# beacon7012.net
KiCad netlist of a schematic drawn in EAGLE
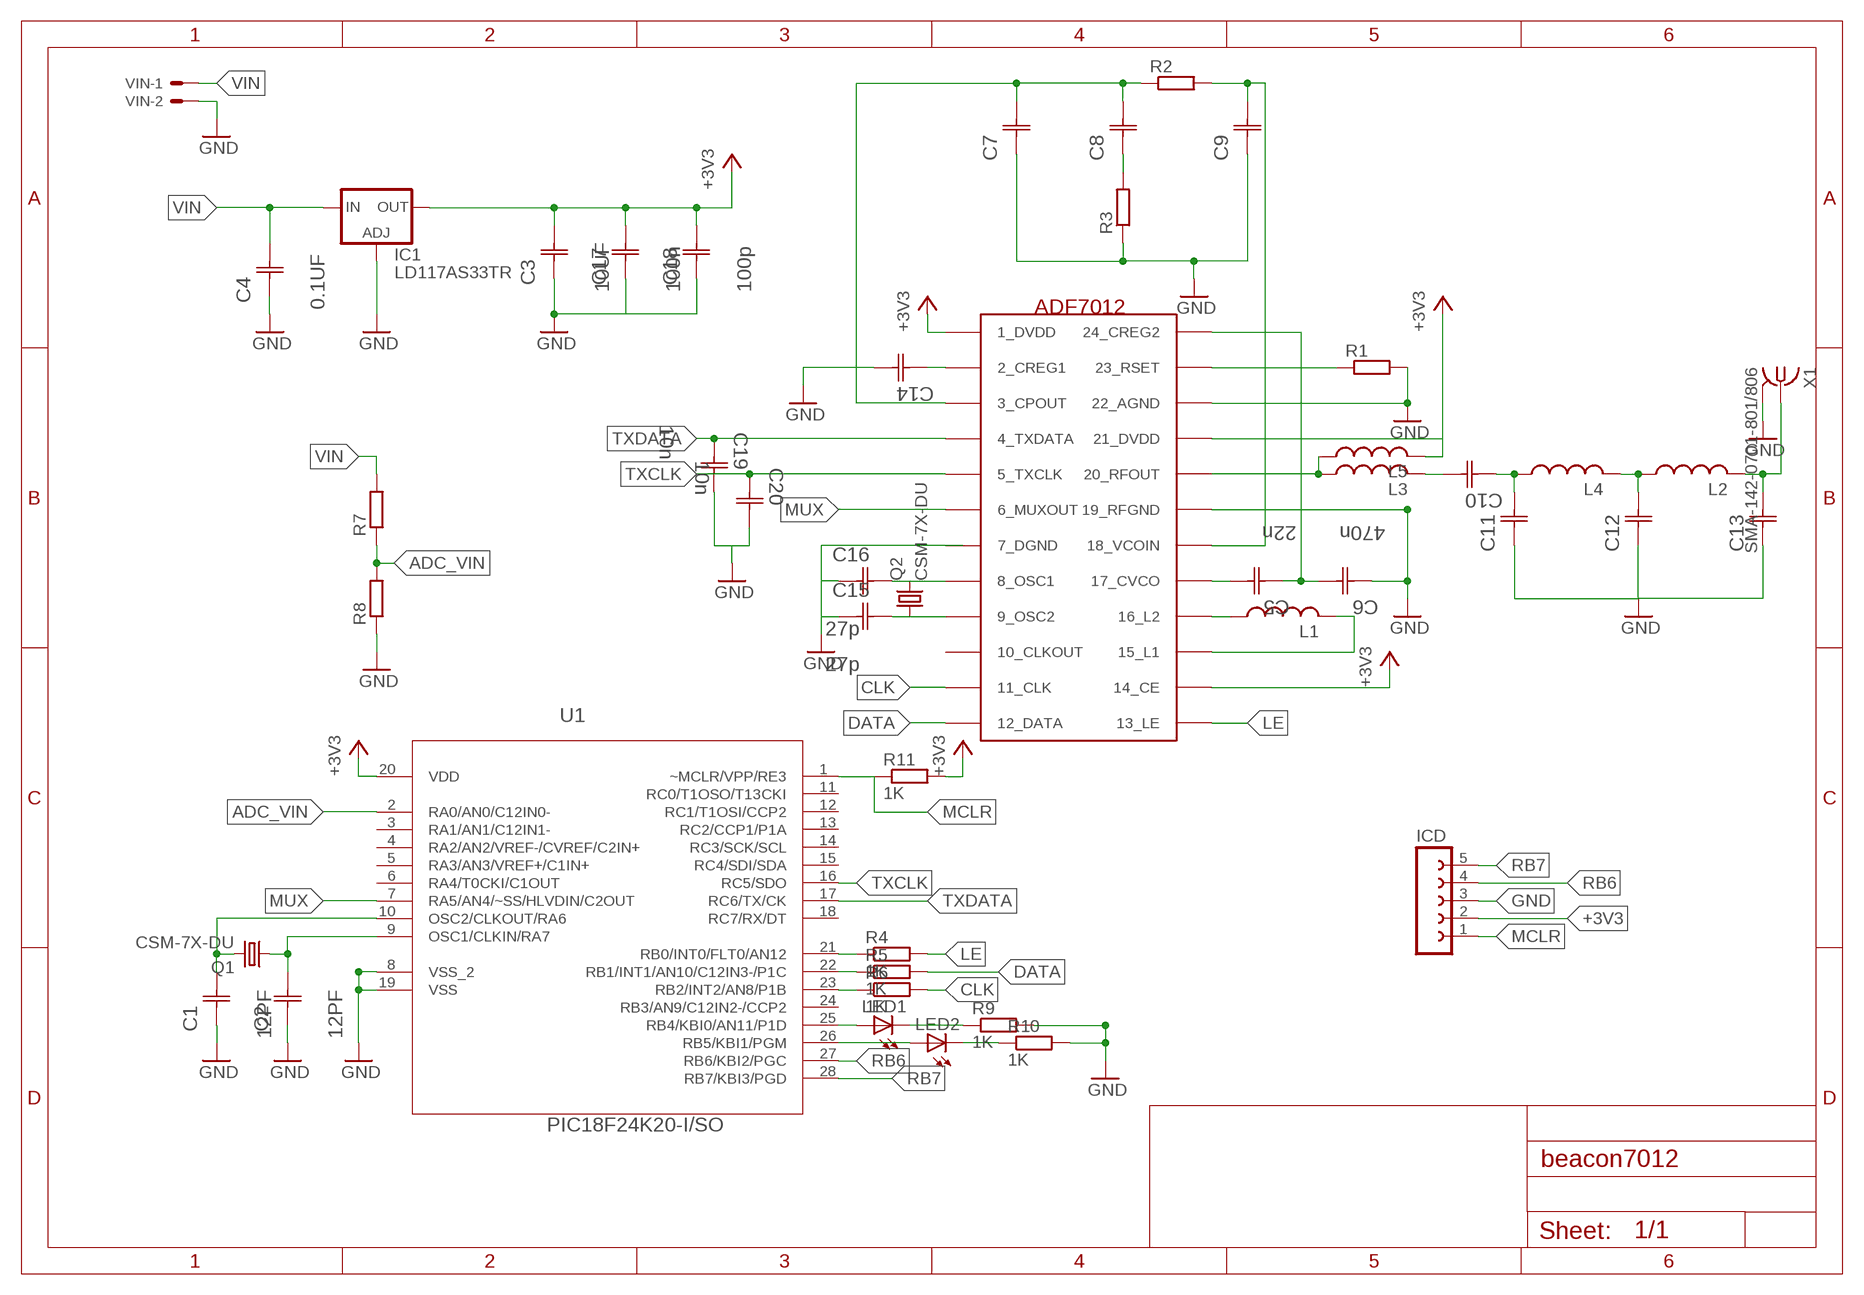
[diagram p0: schematic, sheet 1]

(export (version "E")
  (design (tool "Eeschema 10.0.6"))
  (components
    (comp (ref "C1")
      (value "12PF")
      (footprint "eagle-import:CAPC2012X94N")
      (fields (field (name "MPN") "0805YA120JAT2A") (field (name "TOLERANCE") "± 5%"))
      (libsource (lib "eagle-import") (part "0805YA120JAT2A"))
    )
    (comp (ref "C2")
      (value "12PF")
      (footprint "eagle-import:CAPC2012X94N")
      (fields (field (name "MPN") "0805YA120JAT2A") (field (name "TOLERANCE") "± 5%"))
      (libsource (lib "eagle-import") (part "0805YA120JAT2A"))
    )
    (comp (ref "C3")
      (value "10UF")
      (footprint "eagle-import:CAPC2013X140N")
      (fields (field (name "MPN") "0805YD106MAT2A") (field (name "TOLERANCE") "±20%"))
      (libsource (lib "eagle-import") (part "0805YD106MAT2A"))
    )
    (comp (ref "C4")
      (value "0.1UF")
      (footprint "eagle-import:CAPC2012X94N")
      (fields (field (name "MPN") "0805ZC104MAT2A") (field (name "TOLERANCE") "±20%"))
      (libsource (lib "eagle-import") (part "0805ZC104MAT2A"))
    )
    (comp (ref "C5")
      (value "22n")
      (footprint "eagle-import:CAPC2012X94N")
      (fields (field (name "MPN") "0805ZC104MAT2A") (field (name "TOLERANCE") "±20%"))
      (libsource (lib "eagle-import") (part "0805ZC104MAT2A"))
    )
    (comp (ref "C6")
      (value "470n")
      (footprint "eagle-import:CAPC2012X94N")
      (fields (field (name "MPN") "0805ZC104MAT2A") (field (name "TOLERANCE") "±20%"))
      (libsource (lib "eagle-import") (part "0805ZC104MAT2A"))
    )
    (comp (ref "C7")
      (value "0805YD106MAT2A")
      (footprint "eagle-import:CAPC2013X140N")
      (fields (field (name "TOLERANCE") "±20%"))
      (libsource (lib "eagle-import") (part "0805YD106MAT2A"))
    )
    (comp (ref "C8")
      (value "0805YD106MAT2A")
      (footprint "eagle-import:CAPC2013X140N")
      (fields (field (name "TOLERANCE") "±20%"))
      (libsource (lib "eagle-import") (part "0805YD106MAT2A"))
    )
    (comp (ref "C9")
      (value "0805YD106MAT2A")
      (footprint "eagle-import:CAPC2013X140N")
      (fields (field (name "TOLERANCE") "±20%"))
      (libsource (lib "eagle-import") (part "0805YD106MAT2A"))
    )
    (comp (ref "C10")
      (value "0805ZC104MAT2A")
      (footprint "eagle-import:CAPC2012X94N")
      (fields (field (name "TOLERANCE") "±20%"))
      (libsource (lib "eagle-import") (part "0805ZC104MAT2A"))
    )
    (comp (ref "C11")
      (value "0805YD106MAT2A")
      (footprint "eagle-import:CAPC2013X140N")
      (fields (field (name "TOLERANCE") "±20%"))
      (libsource (lib "eagle-import") (part "0805YD106MAT2A"))
    )
    (comp (ref "C12")
      (value "0805YD106MAT2A")
      (footprint "eagle-import:CAPC2013X140N")
      (fields (field (name "TOLERANCE") "±20%"))
      (libsource (lib "eagle-import") (part "0805YD106MAT2A"))
    )
    (comp (ref "C13")
      (value "0805YD106MAT2A")
      (footprint "eagle-import:CAPC2013X140N")
      (fields (field (name "TOLERANCE") "±20%"))
      (libsource (lib "eagle-import") (part "0805YD106MAT2A"))
    )
    (comp (ref "C14")
      (value "0805ZC104MAT2A")
      (footprint "eagle-import:CAPC2012X94N")
      (fields (field (name "TOLERANCE") "±20%"))
      (libsource (lib "eagle-import") (part "0805ZC104MAT2A"))
    )
    (comp (ref "C15")
      (value "27p")
      (footprint "eagle-import:CAPC2012X94N")
      (fields (field (name "MPN") "0805ZC104MAT2A") (field (name "TOLERANCE") "±20%"))
      (libsource (lib "eagle-import") (part "0805ZC104MAT2A"))
    )
    (comp (ref "C16")
      (value "27p")
      (footprint "eagle-import:CAPC2012X94N")
      (fields (field (name "MPN") "0805ZC104MAT2A") (field (name "TOLERANCE") "±20%"))
      (libsource (lib "eagle-import") (part "0805ZC104MAT2A"))
    )
    (comp (ref "C17")
      (value "100n")
      (footprint "eagle-import:CAPC2013X140N")
      (fields (field (name "MPN") "0805YD106MAT2A") (field (name "TOLERANCE") "±20%"))
      (libsource (lib "eagle-import") (part "0805YD106MAT2A"))
    )
    (comp (ref "C18")
      (value "100p")
      (footprint "eagle-import:CAPC2013X140N")
      (fields (field (name "MPN") "0805YD106MAT2A") (field (name "TOLERANCE") "±20%"))
      (libsource (lib "eagle-import") (part "0805YD106MAT2A"))
    )
    (comp (ref "C19")
      (value "10n")
      (footprint "eagle-import:CAPC2012X94N")
      (fields (field (name "MPN") "0805ZC104MAT2A") (field (name "TOLERANCE") "±20%"))
      (libsource (lib "eagle-import") (part "0805ZC104MAT2A"))
    )
    (comp (ref "C20")
      (value "10n")
      (footprint "eagle-import:CAPC2012X94N")
      (fields (field (name "MPN") "0805ZC104MAT2A") (field (name "TOLERANCE") "±20%"))
      (libsource (lib "eagle-import") (part "0805ZC104MAT2A"))
    )
    (comp (ref "IC1")
      (value "LD117AS33TR")
      (footprint "eagle-import:SOT223")
      (libsource (lib "eagle-import") (part "LD117A?S33TR"))
    )
    (comp (ref "ICD")
      (value "FE05-1")
      (footprint "eagle-import:FE05-1")
      (libsource (lib "eagle-import") (part "FE05-1"))
    )
    (comp (ref "L1")
      (value "L-USL2825P")
      (footprint "eagle-import:L2825P")
      (libsource (lib "eagle-import") (part "L-USL2825P"))
    )
    (comp (ref "L2")
      (value "L-USL2825P")
      (footprint "eagle-import:L2825P")
      (libsource (lib "eagle-import") (part "L-USL2825P"))
    )
    (comp (ref "L3")
      (value "L-USL2825P")
      (footprint "eagle-import:L2825P")
      (libsource (lib "eagle-import") (part "L-USL2825P"))
    )
    (comp (ref "L4")
      (value "L-USL2825P")
      (footprint "eagle-import:L2825P")
      (libsource (lib "eagle-import") (part "L-USL2825P"))
    )
    (comp (ref "L5")
      (value "L-USL2825P")
      (footprint "eagle-import:L2825P")
      (libsource (lib "eagle-import") (part "L-USL2825P"))
    )
    (comp (ref "LED1")
      (value "LEDSML0805")
      (footprint "eagle-import:SML0805")
      (libsource (lib "eagle-import") (part "LEDSML0805"))
    )
    (comp (ref "LED2")
      (value "LEDSML0805")
      (footprint "eagle-import:SML0805")
      (libsource (lib "eagle-import") (part "LEDSML0805"))
    )
    (comp (ref "Q1")
      (value "CSM-7X-DU")
      (footprint "eagle-import:CSM-7X-DU")
      (libsource (lib "eagle-import") (part "CSM-7X-DU"))
    )
    (comp (ref "Q2")
      (value "CSM-7X-DU")
      (footprint "eagle-import:CSM-7X-DU")
      (libsource (lib "eagle-import") (part "CSM-7X-DU"))
    )
    (comp (ref "R1")
      (value "R-EU_R0805")
      (footprint "eagle-import:R0805")
      (libsource (lib "eagle-import") (part "R-EU_R0805"))
    )
    (comp (ref "R2")
      (value "R-EU_R0805")
      (footprint "eagle-import:R0805")
      (libsource (lib "eagle-import") (part "R-EU_R0805"))
    )
    (comp (ref "R3")
      (value "R-EU_R0805")
      (footprint "eagle-import:R0805")
      (libsource (lib "eagle-import") (part "R-EU_R0805"))
    )
    (comp (ref "R4")
      (value "1K")
      (footprint "eagle-import:R0805")
      (libsource (lib "eagle-import") (part "R-EU_R0805"))
    )
    (comp (ref "R5")
      (value "1K")
      (footprint "eagle-import:R0805")
      (libsource (lib "eagle-import") (part "R-EU_R0805"))
    )
    (comp (ref "R6")
      (value "1K")
      (footprint "eagle-import:R0805")
      (libsource (lib "eagle-import") (part "R-EU_R0805"))
    )
    (comp (ref "R7")
      (value "R-EU_R0805")
      (footprint "eagle-import:R0805")
      (libsource (lib "eagle-import") (part "R-EU_R0805"))
    )
    (comp (ref "R8")
      (value "R-EU_R0805")
      (footprint "eagle-import:R0805")
      (libsource (lib "eagle-import") (part "R-EU_R0805"))
    )
    (comp (ref "R9")
      (value "1K")
      (footprint "eagle-import:R0805")
      (libsource (lib "eagle-import") (part "R-EU_R0805"))
    )
    (comp (ref "R10")
      (value "1K")
      (footprint "eagle-import:R0805")
      (libsource (lib "eagle-import") (part "R-EU_R0805"))
    )
    (comp (ref "R11")
      (value "1K")
      (footprint "eagle-import:R0805")
      (libsource (lib "eagle-import") (part "R-EU_R0805"))
    )
    (comp (ref "U$1")
      (value "ADF7012")
      (footprint "eagle-import:ADF7012")
      (libsource (lib "eagle-import") (part "ADF7012"))
    )
    (comp (ref "U1")
      (value "PIC18F24K20-I/SO")
      (footprint "eagle-import:SOIC127P1030X265-28N")
      (libsource (lib "eagle-import") (part "PIC18F24K20-I/SO"))
    )
    (comp (ref "VIN")
      (value "KK-156-2")
      (footprint "eagle-import:KK-156-2")
      (libsource (lib "eagle-import") (part "KK-156-2"))
    )
    (comp (ref "X1")
      (value "SMA-142-0701-801/806")
      (footprint "eagle-import:J502-ND-142-0701-801_806")
      (fields (field (name "MF") "JOHNSON COMPONENTS") (field (name "MPN") "142-0701-801"))
      (libsource (lib "eagle-import") (part "SMA-142-0701-801/806"))
    )
  )
  (nets
    (net (code "1") (name "+3V3") (class "Default")
      (node (ref "C17") (pin "2") (pinfunction "C2_2") (pintype "passive"))
      (node (ref "C18") (pin "2") (pinfunction "C2_2") (pintype "passive"))
      (node (ref "C3") (pin "2") (pinfunction "C2_2") (pintype "passive"))
      (node (ref "IC1") (pin "4") (pinfunction "OUT_4") (pintype "passive"))
      (node (ref "ICD") (pin "2") (pinfunction "2_2") (pintype "passive"))
      (node (ref "L5") (pin "2") (pinfunction "2_2") (pintype "passive"))
      (node (ref "R11") (pin "2") (pinfunction "2_2") (pintype "passive"))
      (node (ref "U$1") (pin "14_CE") (pinfunction "14_CE_14_CE") (pintype "bidirectional"))
      (node (ref "U$1") (pin "1_DVDD") (pinfunction "1_DVDD_1_DVDD") (pintype "bidirectional"))
      (node (ref "U$1") (pin "21_DVDD") (pinfunction "21_DVDD_21_DVDD") (pintype "bidirectional"))
      (node (ref "U1") (pin "20") (pinfunction "VDD_20") (pintype "power_in"))
    )
    (net (code "2") (name "ADC_VIN") (class "Default")
      (node (ref "R7") (pin "1") (pinfunction "1_1") (pintype "passive"))
      (node (ref "R8") (pin "2") (pinfunction "2_2") (pintype "passive"))
      (node (ref "U1") (pin "2") (pinfunction "RA0/AN0/C12IN0-_2") (pintype "bidirectional"))
    )
    (net (code "3") (name "CLK") (class "Default")
      (node (ref "R6") (pin "2") (pinfunction "2_2") (pintype "passive"))
      (node (ref "U$1") (pin "11_CLK") (pinfunction "11_CLK_11_CLK") (pintype "bidirectional"))
    )
    (net (code "4") (name "DATA") (class "Default")
      (node (ref "R5") (pin "2") (pinfunction "2_2") (pintype "passive"))
      (node (ref "U$1") (pin "12_DATA") (pinfunction "12_DATA_12_DATA") (pintype "bidirectional"))
    )
    (net (code "5") (name "GND") (class "Default")
      (node (ref "C1") (pin "1") (pinfunction "C1_1") (pintype "passive"))
      (node (ref "C11") (pin "1") (pinfunction "C1_1") (pintype "passive"))
      (node (ref "C12") (pin "1") (pinfunction "C1_1") (pintype "passive"))
      (node (ref "C13") (pin "1") (pinfunction "C1_1") (pintype "passive"))
      (node (ref "C14") (pin "2") (pinfunction "C2_2") (pintype "passive"))
      (node (ref "C15") (pin "1") (pinfunction "C1_1") (pintype "passive"))
      (node (ref "C16") (pin "1") (pinfunction "C1_1") (pintype "passive"))
      (node (ref "C17") (pin "1") (pinfunction "C1_1") (pintype "passive"))
      (node (ref "C18") (pin "1") (pinfunction "C1_1") (pintype "passive"))
      (node (ref "C19") (pin "2") (pinfunction "C2_2") (pintype "passive"))
      (node (ref "C2") (pin "1") (pinfunction "C1_1") (pintype "passive"))
      (node (ref "C20") (pin "2") (pinfunction "C2_2") (pintype "passive"))
      (node (ref "C3") (pin "1") (pinfunction "C1_1") (pintype "passive"))
      (node (ref "C4") (pin "1") (pinfunction "C1_1") (pintype "passive"))
      (node (ref "C6") (pin "1") (pinfunction "C1_1") (pintype "passive"))
      (node (ref "C7") (pin "1") (pinfunction "C1_1") (pintype "passive"))
      (node (ref "C9") (pin "1") (pinfunction "C1_1") (pintype "passive"))
      (node (ref "IC1") (pin "1") (pinfunction "ADJ_1") (pintype "input"))
      (node (ref "ICD") (pin "3") (pinfunction "3_3") (pintype "passive"))
      (node (ref "R1") (pin "2") (pinfunction "2_2") (pintype "passive"))
      (node (ref "R10") (pin "2") (pinfunction "2_2") (pintype "passive"))
      (node (ref "R3") (pin "1") (pinfunction "1_1") (pintype "passive"))
      (node (ref "R8") (pin "1") (pinfunction "1_1") (pintype "passive"))
      (node (ref "R9") (pin "2") (pinfunction "2_2") (pintype "passive"))
      (node (ref "U$1") (pin "19_RFGND") (pinfunction "19_RFGND_19_RFGND") (pintype "bidirectional"))
      (node (ref "U$1") (pin "22_AGND") (pinfunction "22_AGND_22_AGND") (pintype "bidirectional"))
      (node (ref "U1") (pin "19") (pinfunction "VSS_19") (pintype "power_in"))
      (node (ref "U1") (pin "8") (pinfunction "VSS_2_8") (pintype "power_in"))
      (node (ref "VIN") (pin "2") (pinfunction "S_2") (pintype "passive"))
      (node (ref "X1") (pin "G@1") (pinfunction "2_G@1") (pintype "passive"))
      (node (ref "X1") (pin "G@2") (pinfunction "2_G@2") (pintype "passive"))
      (node (ref "X1") (pin "G@3") (pinfunction "2_G@3") (pintype "passive"))
      (node (ref "X1") (pin "G@4") (pinfunction "2_G@4") (pintype "passive"))
    )
    (net (code "6") (name "LE") (class "Default")
      (node (ref "R4") (pin "2") (pinfunction "2_2") (pintype "passive"))
      (node (ref "U$1") (pin "13_LE") (pinfunction "13_LE_13_LE") (pintype "bidirectional"))
    )
    (net (code "7") (name "MCLR") (class "Default")
      (node (ref "ICD") (pin "1") (pinfunction "1_1") (pintype "passive"))
      (node (ref "R11") (pin "1") (pinfunction "1_1") (pintype "passive"))
      (node (ref "U1") (pin "1") (pinfunction "~{MCLR/VPP/RE3}_1") (pintype "bidirectional"))
    )
    (net (code "8") (name "MUX") (class "Default")
      (node (ref "U$1") (pin "6_MUXOUT") (pinfunction "6_MUXOUT_6_MUXOUT") (pintype "bidirectional"))
      (node (ref "U1") (pin "7") (pinfunction "RA5/AN4/~{SS/HLVDIN/C2OUT}_7") (pintype "bidirectional"))
    )
    (net (code "9") (name "Net-(C1-C2)") (class "Default")
      (node (ref "C1") (pin "2") (pinfunction "C2_2") (pintype "passive"))
      (node (ref "Q1") (pin "2") (pinfunction "2_2") (pintype "passive"))
      (node (ref "U1") (pin "10") (pinfunction "OSC2/CLKOUT/RA6_10") (pintype "bidirectional"))
    )
    (net (code "10") (name "Net-(C2-C2)") (class "Default")
      (node (ref "C2") (pin "2") (pinfunction "C2_2") (pintype "passive"))
      (node (ref "Q1") (pin "1") (pinfunction "1_1") (pintype "passive"))
      (node (ref "U1") (pin "9") (pinfunction "OSC1/CLKIN/RA7_9") (pintype "bidirectional"))
    )
    (net (code "11") (name "Net-(C5-C1)") (class "Default")
      (node (ref "C5") (pin "1") (pinfunction "C1_1") (pintype "passive"))
      (node (ref "C6") (pin "2") (pinfunction "C2_2") (pintype "passive"))
      (node (ref "U$1") (pin "24_CREG2") (pinfunction "24_CREG2_24_CREG2") (pintype "bidirectional"))
    )
    (net (code "12") (name "Net-(C5-C2)") (class "Default")
      (node (ref "C5") (pin "2") (pinfunction "C2_2") (pintype "passive"))
      (node (ref "U$1") (pin "17_CVCO") (pinfunction "17_CVCO_17_CVCO") (pintype "bidirectional"))
    )
    (net (code "13") (name "Net-(C7-C2)") (class "Default")
      (node (ref "C7") (pin "2") (pinfunction "C2_2") (pintype "passive"))
      (node (ref "C8") (pin "2") (pinfunction "C2_2") (pintype "passive"))
      (node (ref "R2") (pin "1") (pinfunction "1_1") (pintype "passive"))
      (node (ref "U$1") (pin "3_CPOUT") (pinfunction "3_CPOUT_3_CPOUT") (pintype "bidirectional"))
    )
    (net (code "14") (name "Net-(C8-C1)") (class "Default")
      (node (ref "C8") (pin "1") (pinfunction "C1_1") (pintype "passive"))
      (node (ref "R3") (pin "2") (pinfunction "2_2") (pintype "passive"))
    )
    (net (code "15") (name "Net-(C9-C2)") (class "Default")
      (node (ref "C9") (pin "2") (pinfunction "C2_2") (pintype "passive"))
      (node (ref "R2") (pin "2") (pinfunction "2_2") (pintype "passive"))
      (node (ref "U$1") (pin "18_VCOIN") (pinfunction "18_VCOIN_18_VCOIN") (pintype "bidirectional"))
    )
    (net (code "16") (name "Net-(C10-C1)") (class "Default")
      (node (ref "C10") (pin "1") (pinfunction "C1_1") (pintype "passive"))
      (node (ref "C11") (pin "2") (pinfunction "C2_2") (pintype "passive"))
      (node (ref "L4") (pin "1") (pinfunction "1_1") (pintype "passive"))
    )
    (net (code "17") (name "Net-(C10-C2)") (class "Default")
      (node (ref "C10") (pin "2") (pinfunction "C2_2") (pintype "passive"))
      (node (ref "L3") (pin "2") (pinfunction "2_2") (pintype "passive"))
    )
    (net (code "18") (name "Net-(C12-C2)") (class "Default")
      (node (ref "C12") (pin "2") (pinfunction "C2_2") (pintype "passive"))
      (node (ref "L2") (pin "1") (pinfunction "1_1") (pintype "passive"))
      (node (ref "L4") (pin "2") (pinfunction "2_2") (pintype "passive"))
    )
    (net (code "19") (name "Net-(C13-C2)") (class "Default")
      (node (ref "C13") (pin "2") (pinfunction "C2_2") (pintype "passive"))
      (node (ref "L2") (pin "2") (pinfunction "2_2") (pintype "passive"))
      (node (ref "X1") (pin "1") (pinfunction "1_1") (pintype "passive"))
    )
    (net (code "20") (name "Net-(C14-C1)") (class "Default")
      (node (ref "C14") (pin "1") (pinfunction "C1_1") (pintype "passive"))
      (node (ref "U$1") (pin "2_CREG1") (pinfunction "2_CREG1_2_CREG1") (pintype "bidirectional"))
    )
    (net (code "21") (name "Net-(C15-C2)") (class "Default")
      (node (ref "C15") (pin "2") (pinfunction "C2_2") (pintype "passive"))
      (node (ref "Q2") (pin "1") (pinfunction "1_1") (pintype "passive"))
      (node (ref "U$1") (pin "9_OSC2") (pinfunction "9_OSC2_9_OSC2") (pintype "bidirectional"))
    )
    (net (code "22") (name "Net-(C16-C2)") (class "Default")
      (node (ref "C16") (pin "2") (pinfunction "C2_2") (pintype "passive"))
      (node (ref "Q2") (pin "2") (pinfunction "2_2") (pintype "passive"))
      (node (ref "U$1") (pin "8_OSC1") (pinfunction "8_OSC1_8_OSC1") (pintype "bidirectional"))
    )
    (net (code "23") (name "Net-(L1-Pad1)") (class "Default")
      (node (ref "L1") (pin "1") (pinfunction "1_1") (pintype "passive"))
      (node (ref "U$1") (pin "16_L2") (pinfunction "16_L2_16_L2") (pintype "bidirectional"))
    )
    (net (code "24") (name "Net-(L1-Pad2)") (class "Default")
      (node (ref "L1") (pin "2") (pinfunction "2_2") (pintype "passive"))
      (node (ref "U$1") (pin "15_L1") (pinfunction "15_L1_15_L1") (pintype "bidirectional"))
    )
    (net (code "25") (name "Net-(L3-Pad1)") (class "Default")
      (node (ref "L3") (pin "1") (pinfunction "1_1") (pintype "passive"))
      (node (ref "L5") (pin "1") (pinfunction "1_1") (pintype "passive"))
      (node (ref "U$1") (pin "20_RFOUT") (pinfunction "20_RFOUT_20_RFOUT") (pintype "bidirectional"))
    )
    (net (code "26") (name "Net-(LED1-PadC)") (class "Default")
      (node (ref "LED1") (pin "C") (pinfunction "C_C") (pintype "passive"))
      (node (ref "R9") (pin "1") (pinfunction "1_1") (pintype "passive"))
    )
    (net (code "27") (name "Net-(LED2-PadC)") (class "Default")
      (node (ref "LED2") (pin "C") (pinfunction "C_C") (pintype "passive"))
      (node (ref "R10") (pin "1") (pinfunction "1_1") (pintype "passive"))
    )
    (net (code "28") (name "Net-(R1-Pad1)") (class "Default")
      (node (ref "R1") (pin "1") (pinfunction "1_1") (pintype "passive"))
      (node (ref "U$1") (pin "23_RSET") (pinfunction "23_RSET_23_RSET") (pintype "bidirectional"))
    )
    (net (code "29") (name "Net-(U1-RB0{slash}INT0{slash}FLT0{slash}AN12)") (class "Default")
      (node (ref "R4") (pin "1") (pinfunction "1_1") (pintype "passive"))
      (node (ref "U1") (pin "21") (pinfunction "RB0/INT0/FLT0/AN12_21") (pintype "bidirectional"))
    )
    (net (code "30") (name "Net-(U1-RB1{slash}INT1{slash}AN10{slash}C12IN3-{slash}P1C)") (class "Default")
      (node (ref "R5") (pin "1") (pinfunction "1_1") (pintype "passive"))
      (node (ref "U1") (pin "22") (pinfunction "RB1/INT1/AN10/C12IN3-/P1C_22") (pintype "bidirectional"))
    )
    (net (code "31") (name "Net-(U1-RB2{slash}INT2{slash}AN8{slash}P1B)") (class "Default")
      (node (ref "R6") (pin "1") (pinfunction "1_1") (pintype "passive"))
      (node (ref "U1") (pin "23") (pinfunction "RB2/INT2/AN8/P1B_23") (pintype "bidirectional"))
    )
    (net (code "32") (name "Net-(U1-RB4{slash}KBI0{slash}AN11{slash}P1D)") (class "Default")
      (node (ref "LED1") (pin "A") (pinfunction "A_A") (pintype "passive"))
      (node (ref "U1") (pin "25") (pinfunction "RB4/KBI0/AN11/P1D_25") (pintype "bidirectional"))
    )
    (net (code "33") (name "Net-(U1-RB5{slash}KBI1{slash}PGM)") (class "Default")
      (node (ref "LED2") (pin "A") (pinfunction "A_A") (pintype "passive"))
      (node (ref "U1") (pin "26") (pinfunction "RB5/KBI1/PGM_26") (pintype "bidirectional"))
    )
    (net (code "34") (name "RB6") (class "Default")
      (node (ref "ICD") (pin "4") (pinfunction "4_4") (pintype "passive"))
      (node (ref "U1") (pin "27") (pinfunction "RB6/KBI2/PGC_27") (pintype "bidirectional"))
    )
    (net (code "35") (name "RB7") (class "Default")
      (node (ref "ICD") (pin "5") (pinfunction "5_5") (pintype "passive"))
      (node (ref "U1") (pin "28") (pinfunction "RB7/KBI3/PGD_28") (pintype "bidirectional"))
    )
    (net (code "36") (name "TXCLK") (class "Default")
      (node (ref "C20") (pin "1") (pinfunction "C1_1") (pintype "passive"))
      (node (ref "U$1") (pin "5_TXCLK") (pinfunction "5_TXCLK_5_TXCLK") (pintype "bidirectional"))
      (node (ref "U1") (pin "16") (pinfunction "RC5/SDO_16") (pintype "bidirectional"))
    )
    (net (code "37") (name "TXDATA") (class "Default")
      (node (ref "C19") (pin "1") (pinfunction "C1_1") (pintype "passive"))
      (node (ref "U$1") (pin "4_TXDATA") (pinfunction "4_TXDATA_4_TXDATA") (pintype "bidirectional"))
      (node (ref "U1") (pin "17") (pinfunction "RC6/TX/CK_17") (pintype "bidirectional"))
    )
    (net (code "38") (name "VIN") (class "Default")
      (node (ref "C4") (pin "2") (pinfunction "C2_2") (pintype "passive"))
      (node (ref "IC1") (pin "3") (pinfunction "IN_3") (pintype "input"))
      (node (ref "R7") (pin "2") (pinfunction "2_2") (pintype "passive"))
      (node (ref "VIN") (pin "1") (pinfunction "S_1") (pintype "passive"))
    )
    (net (code "39") (name "unconnected-(U$1-Pad7_DGND)") (class "Default")
      (node (ref "U$1") (pin "7_DGND") (pinfunction "7_DGND_7_DGND") (pintype "bidirectional"))
    )
    (net (code "40") (name "unconnected-(U$1-Pad10_CLKOUT)") (class "Default")
      (node (ref "U$1") (pin "10_CLKOUT") (pinfunction "10_CLKOUT_10_CLKOUT") (pintype "bidirectional"))
    )
    (net (code "41") (name "unconnected-(U1-RA1{slash}AN1{slash}C12IN1--Pad3)") (class "Default")
      (node (ref "U1") (pin "3") (pinfunction "RA1/AN1/C12IN1-_3") (pintype "bidirectional"))
    )
    (net (code "42") (name "unconnected-(U1-RA2{slash}AN2{slash}VREF-{slash}CVREF{slash}C2IN+-Pad4)") (class "Default")
      (node (ref "U1") (pin "4") (pinfunction "RA2/AN2/VREF-/CVREF/C2IN+_4") (pintype "bidirectional"))
    )
    (net (code "43") (name "unconnected-(U1-RA3{slash}AN3{slash}VREF+{slash}C1IN+-Pad5)") (class "Default")
      (node (ref "U1") (pin "5") (pinfunction "RA3/AN3/VREF+/C1IN+_5") (pintype "bidirectional"))
    )
    (net (code "44") (name "unconnected-(U1-RA4{slash}T0CKI{slash}C1OUT-Pad6)") (class "Default")
      (node (ref "U1") (pin "6") (pinfunction "RA4/T0CKI/C1OUT_6") (pintype "bidirectional"))
    )
    (net (code "45") (name "unconnected-(U1-RB3{slash}AN9{slash}C12IN2-{slash}CCP2-Pad24)") (class "Default")
      (node (ref "U1") (pin "24") (pinfunction "RB3/AN9/C12IN2-/CCP2_24") (pintype "bidirectional"))
    )
    (net (code "46") (name "unconnected-(U1-RC0{slash}T1OSO{slash}T13CKI-Pad11)") (class "Default")
      (node (ref "U1") (pin "11") (pinfunction "RC0/T1OSO/T13CKI_11") (pintype "bidirectional"))
    )
    (net (code "47") (name "unconnected-(U1-RC1{slash}T1OSI{slash}CCP2-Pad12)") (class "Default")
      (node (ref "U1") (pin "12") (pinfunction "RC1/T1OSI/CCP2_12") (pintype "bidirectional"))
    )
    (net (code "48") (name "unconnected-(U1-RC2{slash}CCP1{slash}P1A-Pad13)") (class "Default")
      (node (ref "U1") (pin "13") (pinfunction "RC2/CCP1/P1A_13") (pintype "bidirectional"))
    )
    (net (code "49") (name "unconnected-(U1-RC3{slash}SCK{slash}SCL-Pad14)") (class "Default")
      (node (ref "U1") (pin "14") (pinfunction "RC3/SCK/SCL_14") (pintype "bidirectional"))
    )
    (net (code "50") (name "unconnected-(U1-RC4{slash}SDI{slash}SDA-Pad15)") (class "Default")
      (node (ref "U1") (pin "15") (pinfunction "RC4/SDI/SDA_15") (pintype "bidirectional"))
    )
    (net (code "51") (name "unconnected-(U1-RC7{slash}RX{slash}DT-Pad18)") (class "Default")
      (node (ref "U1") (pin "18") (pinfunction "RC7/RX/DT_18") (pintype "bidirectional"))
    )
  )
)
